# CurrentTrans-board-multi.net
KiCad netlist of a schematic drawn in Altium Designer
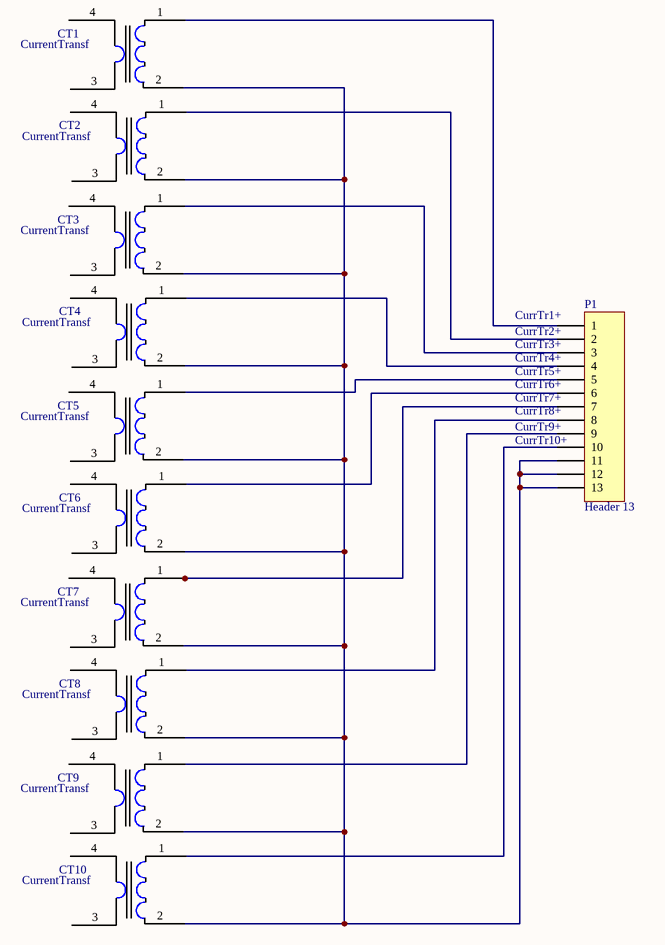
[diagram p0: CurrentTrans-board-multi.SchDoc]

(export (version "E")
  (design (tool "Eeschema 10.0.6"))
  (components
    (comp (ref "CT1")
      (value "CurrentTransf")
      (footprint "CT-ZMCT124")
      (description "CurrentTransf ZMCT116A")
      (fields (field (name "MANUFACTURER") "NanJing ZeMing Electronics Co.Ltd"))
      (libsource (lib "SMLib") (part "CurrentTransf"))
    )
    (comp (ref "CT2")
      (value "CurrentTransf")
      (footprint "CT-ZMCT124")
      (libsource (lib "SMLib") (part "CurrentTransf"))
    )
    (comp (ref "CT3")
      (value "CurrentTransf")
      (footprint "CT-ZMCT124")
      (libsource (lib "SMLib") (part "CurrentTransf"))
    )
    (comp (ref "CT4")
      (value "CurrentTransf")
      (footprint "CT-ZMCT124")
      (libsource (lib "SMLib") (part "CurrentTransf"))
    )
    (comp (ref "CT5")
      (value "CurrentTransf")
      (footprint "CT-ZMCT124")
      (libsource (lib "SMLib") (part "CurrentTransf"))
    )
    (comp (ref "CT6")
      (value "CurrentTransf")
      (footprint "CT-ZMCT124")
      (libsource (lib "SMLib") (part "CurrentTransf"))
    )
    (comp (ref "CT7")
      (value "CurrentTransf")
      (footprint "CT-ZMCT124")
      (fields (field (name "MANUFACTURER") "NanJing ZeMing Electronics Co.Ltd"))
      (libsource (lib "SMLib") (part "CurrentTransf"))
    )
    (comp (ref "CT8")
      (value "CurrentTransf")
      (footprint "CT-ZMCT124")
      (libsource (lib "SMLib") (part "CurrentTransf"))
    )
    (comp (ref "CT9")
      (value "CurrentTransf")
      (footprint "CT-ZMCT124")
      (libsource (lib "SMLib") (part "CurrentTransf"))
    )
    (comp (ref "CT10")
      (value "CurrentTransf")
      (footprint "CT-ZMCT124")
      (libsource (lib "SMLib") (part "CurrentTransf"))
    )
    (comp (ref "P1")
      (value "Header 13")
      (footprint "HDR1X13")
      (description "Header, 13-Pin")
      (fields
        (field (name "MANUFACTURER") "JYR Ecec Co.,Ltd China")
        (field (name "PUBLISHER") "Altium Limited")
      )
      (libsource (lib "Miscellaneous Connectors") (part "Header 13"))
    )
  )
  (nets
    (net (code "1") (name "Net-(CT1-Pad1)") (class "Default")
      (node (ref "CT1") (pin "1") (pinfunction "1_1") (pintype "passive"))
      (node (ref "P1") (pin "1") (pinfunction "1_1") (pintype "passive"))
    )
    (net (code "2") (name "Net-(CT1-Pad2)") (class "Default")
      (node (ref "CT1") (pin "2") (pinfunction "2_2") (pintype "passive"))
      (node (ref "CT10") (pin "2") (pinfunction "2_2") (pintype "passive"))
      (node (ref "CT2") (pin "2") (pinfunction "2_2") (pintype "passive"))
      (node (ref "CT3") (pin "2") (pinfunction "2_2") (pintype "passive"))
      (node (ref "CT4") (pin "2") (pinfunction "2_2") (pintype "passive"))
      (node (ref "CT5") (pin "2") (pinfunction "2_2") (pintype "passive"))
      (node (ref "CT6") (pin "2") (pinfunction "2_2") (pintype "passive"))
      (node (ref "CT7") (pin "2") (pinfunction "2_2") (pintype "passive"))
      (node (ref "CT8") (pin "2") (pinfunction "2_2") (pintype "passive"))
      (node (ref "CT9") (pin "2") (pinfunction "2_2") (pintype "passive"))
      (node (ref "P1") (pin "11") (pinfunction "11_11") (pintype "passive"))
      (node (ref "P1") (pin "12") (pinfunction "12_12") (pintype "passive"))
      (node (ref "P1") (pin "13") (pinfunction "13_13") (pintype "passive"))
    )
    (net (code "3") (name "Net-(CT2-Pad1)") (class "Default")
      (node (ref "CT2") (pin "1") (pinfunction "1_1") (pintype "passive"))
      (node (ref "P1") (pin "2") (pinfunction "2_2") (pintype "passive"))
    )
    (net (code "4") (name "Net-(CT3-Pad1)") (class "Default")
      (node (ref "CT3") (pin "1") (pinfunction "1_1") (pintype "passive"))
      (node (ref "P1") (pin "3") (pinfunction "3_3") (pintype "passive"))
    )
    (net (code "5") (name "Net-(CT4-Pad1)") (class "Default")
      (node (ref "CT4") (pin "1") (pinfunction "1_1") (pintype "passive"))
      (node (ref "P1") (pin "4") (pinfunction "4_4") (pintype "passive"))
    )
    (net (code "6") (name "Net-(CT5-Pad1)") (class "Default")
      (node (ref "CT5") (pin "1") (pinfunction "1_1") (pintype "passive"))
      (node (ref "P1") (pin "5") (pinfunction "5_5") (pintype "passive"))
    )
    (net (code "7") (name "Net-(CT6-Pad1)") (class "Default")
      (node (ref "CT6") (pin "1") (pinfunction "1_1") (pintype "passive"))
      (node (ref "P1") (pin "6") (pinfunction "6_6") (pintype "passive"))
    )
    (net (code "8") (name "Net-(CT7-Pad1)") (class "Default")
      (node (ref "CT7") (pin "1") (pinfunction "1_1") (pintype "passive"))
      (node (ref "P1") (pin "7") (pinfunction "7_7") (pintype "passive"))
    )
    (net (code "9") (name "Net-(CT8-Pad1)") (class "Default")
      (node (ref "CT8") (pin "1") (pinfunction "1_1") (pintype "passive"))
      (node (ref "P1") (pin "8") (pinfunction "8_8") (pintype "passive"))
    )
    (net (code "10") (name "Net-(CT9-Pad1)") (class "Default")
      (node (ref "CT9") (pin "1") (pinfunction "1_1") (pintype "passive"))
      (node (ref "P1") (pin "9") (pinfunction "9_9") (pintype "passive"))
    )
    (net (code "11") (name "Net-(CT10-Pad1)") (class "Default")
      (node (ref "CT10") (pin "1") (pinfunction "1_1") (pintype "passive"))
      (node (ref "P1") (pin "10") (pinfunction "10_10") (pintype "passive"))
    )
    (net (code "12") (name "unconnected-(CT1-Pad3)") (class "Default")
      (node (ref "CT1") (pin "3") (pinfunction "3_3") (pintype "passive"))
    )
    (net (code "13") (name "unconnected-(CT1-Pad4)") (class "Default")
      (node (ref "CT1") (pin "4") (pinfunction "4_4") (pintype "passive"))
    )
    (net (code "14") (name "unconnected-(CT2-Pad3)") (class "Default")
      (node (ref "CT2") (pin "3") (pinfunction "3_3") (pintype "passive"))
    )
    (net (code "15") (name "unconnected-(CT2-Pad4)") (class "Default")
      (node (ref "CT2") (pin "4") (pinfunction "4_4") (pintype "passive"))
    )
    (net (code "16") (name "unconnected-(CT3-Pad3)") (class "Default")
      (node (ref "CT3") (pin "3") (pinfunction "3_3") (pintype "passive"))
    )
    (net (code "17") (name "unconnected-(CT3-Pad4)") (class "Default")
      (node (ref "CT3") (pin "4") (pinfunction "4_4") (pintype "passive"))
    )
    (net (code "18") (name "unconnected-(CT4-Pad3)") (class "Default")
      (node (ref "CT4") (pin "3") (pinfunction "3_3") (pintype "passive"))
    )
    (net (code "19") (name "unconnected-(CT4-Pad4)") (class "Default")
      (node (ref "CT4") (pin "4") (pinfunction "4_4") (pintype "passive"))
    )
    (net (code "20") (name "unconnected-(CT5-Pad3)") (class "Default")
      (node (ref "CT5") (pin "3") (pinfunction "3_3") (pintype "passive"))
    )
    (net (code "21") (name "unconnected-(CT5-Pad4)") (class "Default")
      (node (ref "CT5") (pin "4") (pinfunction "4_4") (pintype "passive"))
    )
    (net (code "22") (name "unconnected-(CT6-Pad3)") (class "Default")
      (node (ref "CT6") (pin "3") (pinfunction "3_3") (pintype "passive"))
    )
    (net (code "23") (name "unconnected-(CT6-Pad4)") (class "Default")
      (node (ref "CT6") (pin "4") (pinfunction "4_4") (pintype "passive"))
    )
    (net (code "24") (name "unconnected-(CT7-Pad3)") (class "Default")
      (node (ref "CT7") (pin "3") (pinfunction "3_3") (pintype "passive"))
    )
    (net (code "25") (name "unconnected-(CT7-Pad4)") (class "Default")
      (node (ref "CT7") (pin "4") (pinfunction "4_4") (pintype "passive"))
    )
    (net (code "26") (name "unconnected-(CT8-Pad3)") (class "Default")
      (node (ref "CT8") (pin "3") (pinfunction "3_3") (pintype "passive"))
    )
    (net (code "27") (name "unconnected-(CT8-Pad4)") (class "Default")
      (node (ref "CT8") (pin "4") (pinfunction "4_4") (pintype "passive"))
    )
    (net (code "28") (name "unconnected-(CT9-Pad3)") (class "Default")
      (node (ref "CT9") (pin "3") (pinfunction "3_3") (pintype "passive"))
    )
    (net (code "29") (name "unconnected-(CT9-Pad4)") (class "Default")
      (node (ref "CT9") (pin "4") (pinfunction "4_4") (pintype "passive"))
    )
    (net (code "30") (name "unconnected-(CT10-Pad3)") (class "Default")
      (node (ref "CT10") (pin "3") (pinfunction "3_3") (pintype "passive"))
    )
    (net (code "31") (name "unconnected-(CT10-Pad4)") (class "Default")
      (node (ref "CT10") (pin "4") (pinfunction "4_4") (pintype "passive"))
    )
  )
)
